# nabijecka1.net
KiCad netlist of a schematic drawn in EAGLE
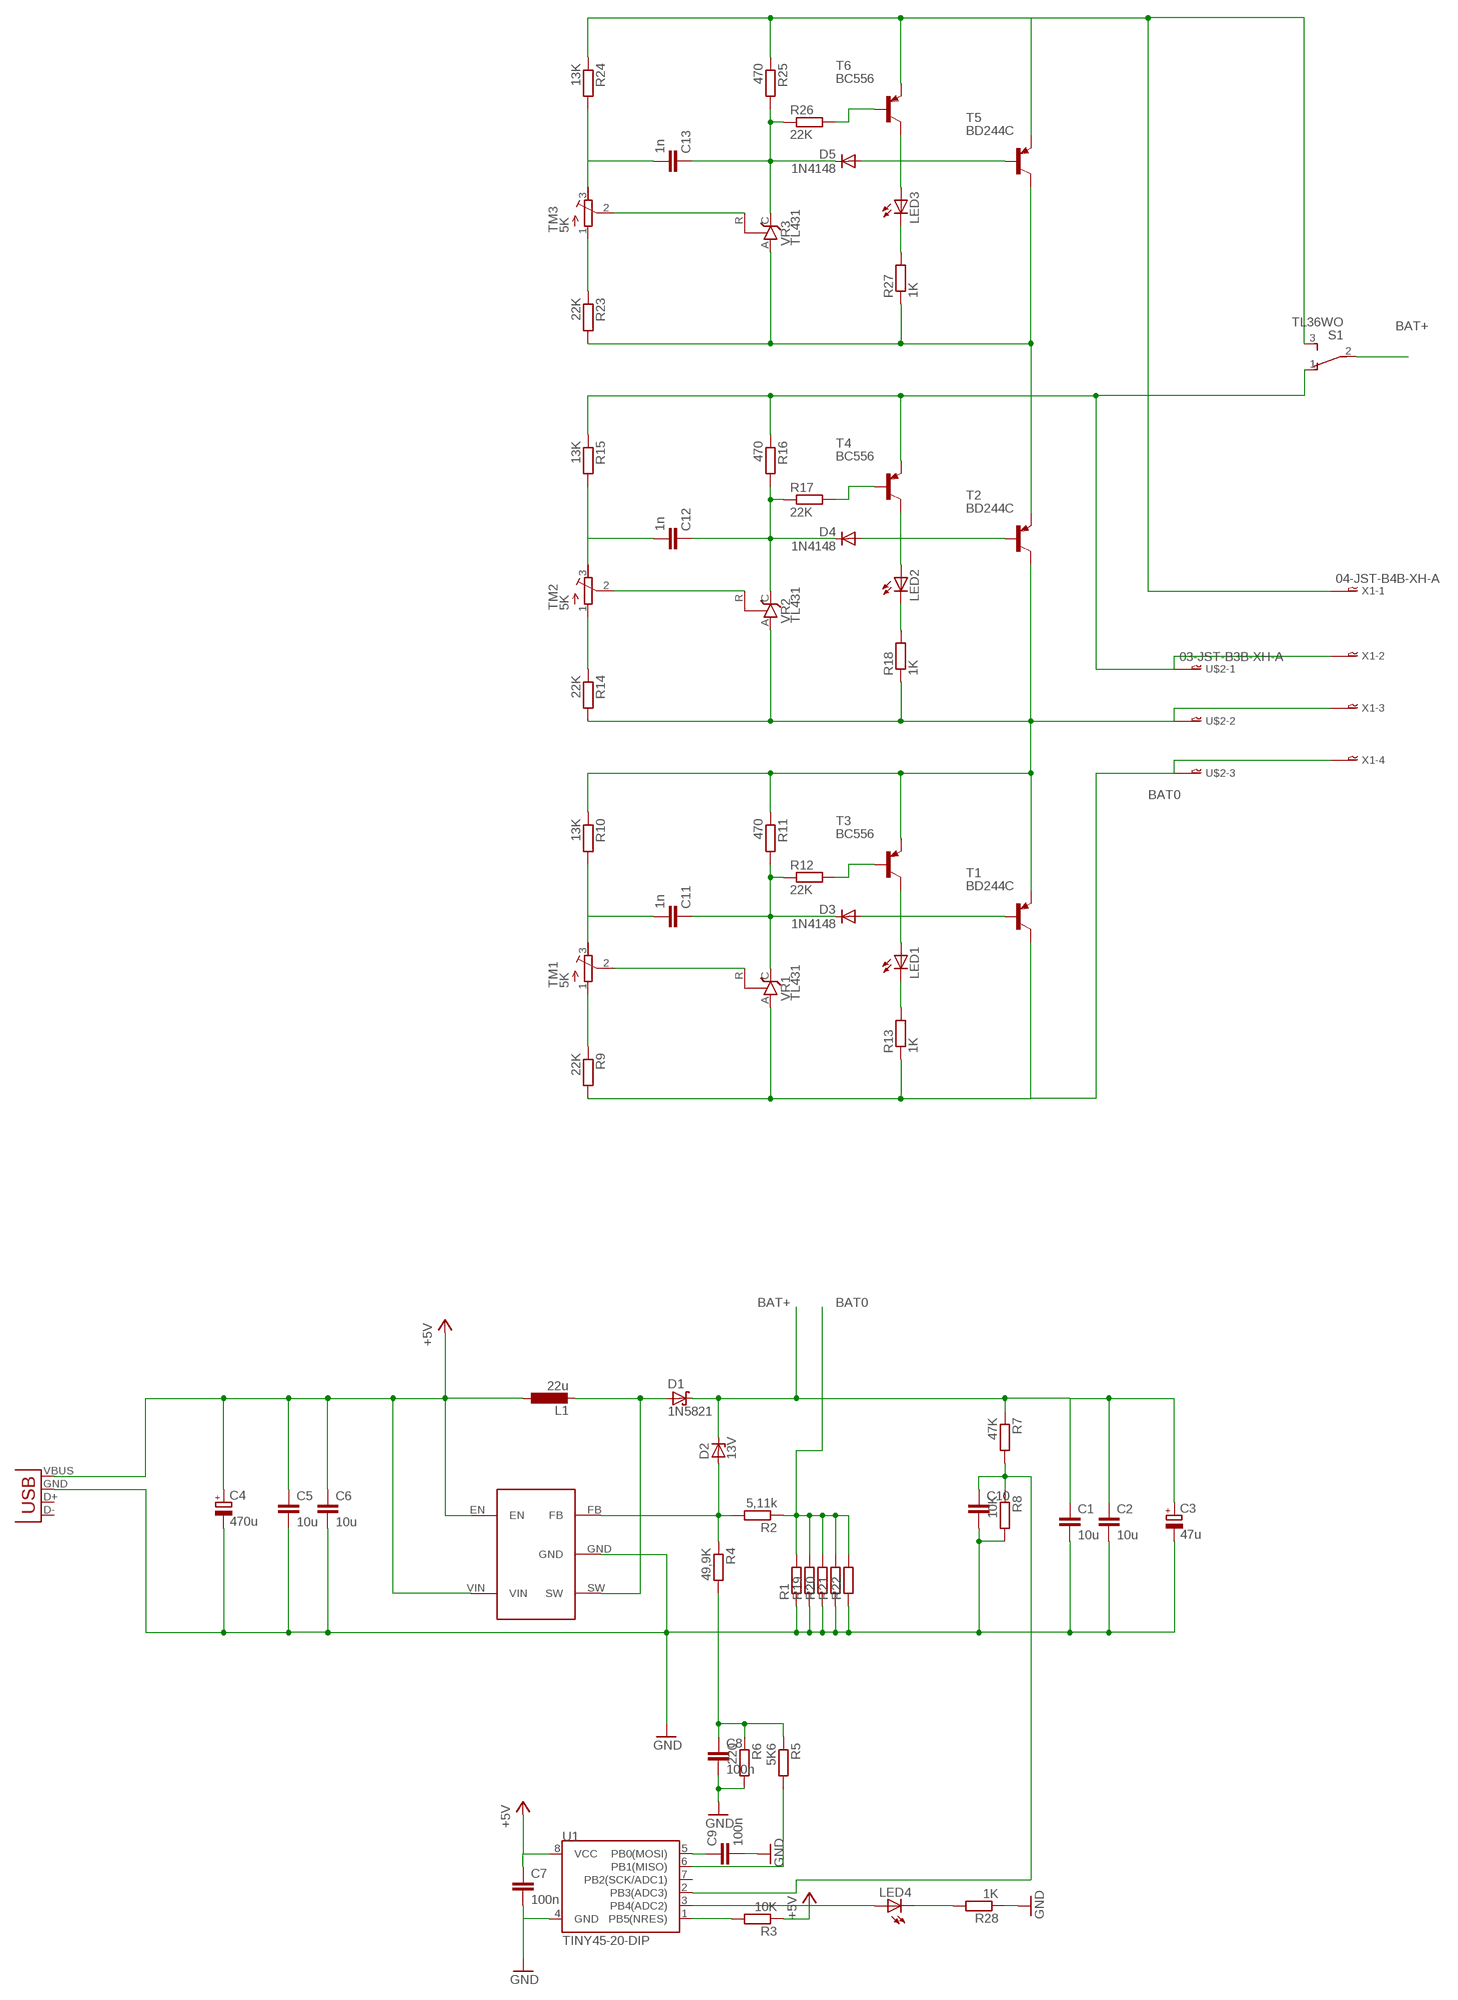
[diagram p0: schematic, sheet 1]

(export (version "E")
  (design (tool "Eeschema 10.0.6"))
  (components
    (comp (ref "C1")
      (value "10u")
      (footprint "eagle-import:C1206")
      (libsource (lib "eagle-import") (part "C-EUC1206"))
    )
    (comp (ref "C2")
      (value "10u")
      (footprint "eagle-import:C1206")
      (libsource (lib "eagle-import") (part "C-EUC1206"))
    )
    (comp (ref "C3")
      (value "47u")
      (footprint "eagle-import:E3,5-8")
      (libsource (lib "eagle-import") (part "CPOL-EUE3.5-8"))
    )
    (comp (ref "C4")
      (value "470u")
      (footprint "eagle-import:E3,5-8")
      (libsource (lib "eagle-import") (part "CPOL-EUE3.5-8"))
    )
    (comp (ref "C5")
      (value "10u")
      (footprint "eagle-import:C1206")
      (libsource (lib "eagle-import") (part "C-EUC1206"))
    )
    (comp (ref "C6")
      (value "10u")
      (footprint "eagle-import:C1206")
      (libsource (lib "eagle-import") (part "C-EUC1206"))
    )
    (comp (ref "C7")
      (value "100n")
      (footprint "eagle-import:C0805")
      (libsource (lib "eagle-import") (part "C-EUC0805"))
    )
    (comp (ref "C8")
      (value "100n")
      (footprint "eagle-import:C1206")
      (libsource (lib "eagle-import") (part "C-EUC1206"))
    )
    (comp (ref "C9")
      (value "100n")
      (footprint "eagle-import:C0805")
      (libsource (lib "eagle-import") (part "C-EUC0805"))
    )
    (comp (ref "C10")
      (value "C-EUC1206")
      (footprint "eagle-import:C1206")
      (libsource (lib "eagle-import") (part "C-EUC1206"))
    )
    (comp (ref "C11")
      (value "1n")
      (footprint "eagle-import:C1206")
      (libsource (lib "eagle-import") (part "C-EUC1206"))
    )
    (comp (ref "C12")
      (value "1n")
      (footprint "eagle-import:C1206")
      (libsource (lib "eagle-import") (part "C-EUC1206"))
    )
    (comp (ref "C13")
      (value "1n")
      (footprint "eagle-import:C1206")
      (libsource (lib "eagle-import") (part "C-EUC1206"))
    )
    (comp (ref "D1")
      (value "1N5821")
      (footprint "eagle-import:DO35-7")
      (libsource (lib "eagle-import") (part "SCHOTTKY-DIODEDO35-7"))
    )
    (comp (ref "D2")
      (value "13V")
      (footprint "eagle-import:SOD80C")
      (libsource (lib "eagle-import") (part "ZENER-DIODESOD80C"))
    )
    (comp (ref "D3")
      (value "1N4148")
      (footprint "eagle-import:SOD80C")
      (libsource (lib "eagle-import") (part "DIODE-SOD80C"))
    )
    (comp (ref "D4")
      (value "1N4148")
      (footprint "eagle-import:SOD80C")
      (libsource (lib "eagle-import") (part "DIODE-SOD80C"))
    )
    (comp (ref "D5")
      (value "1N4148")
      (footprint "eagle-import:SOD80C")
      (libsource (lib "eagle-import") (part "DIODE-SOD80C"))
    )
    (comp (ref "JP2")
      (value "USB-A-H")
      (footprint "eagle-import:USB-A-H")
      (libsource (lib "eagle-import") (part "USB-A-H"))
    )
    (comp (ref "L1")
      (value "22u")
      (footprint "eagle-import:POWER-CHOKE_WE-TPC")
      (libsource (lib "eagle-import") (part "L-EUWE-TPC"))
    )
    (comp (ref "LED1")
      (value "LED3MM")
      (footprint "eagle-import:LED3MM")
      (libsource (lib "eagle-import") (part "LED3MM"))
    )
    (comp (ref "LED2")
      (value "LED3MM")
      (footprint "eagle-import:LED3MM")
      (libsource (lib "eagle-import") (part "LED3MM"))
    )
    (comp (ref "LED3")
      (value "LED3MM")
      (footprint "eagle-import:LED3MM")
      (libsource (lib "eagle-import") (part "LED3MM"))
    )
    (comp (ref "LED4")
      (value "LED3MM")
      (footprint "eagle-import:LED3MM")
      (libsource (lib "eagle-import") (part "LED3MM"))
    )
    (comp (ref "R1")
      (value "R-EU_0204/7")
      (footprint "eagle-import:0204_7")
      (libsource (lib "eagle-import") (part "R-EU_0204/7"))
    )
    (comp (ref "R2")
      (value "5,11k")
      (footprint "eagle-import:0204_5")
      (libsource (lib "eagle-import") (part "R-EU_0204/5"))
    )
    (comp (ref "R3")
      (value "10K")
      (footprint "eagle-import:R0805")
      (libsource (lib "eagle-import") (part "R-EU_R0805"))
    )
    (comp (ref "R4")
      (value "49,9K")
      (footprint "eagle-import:0204_5")
      (libsource (lib "eagle-import") (part "R-EU_0204/5"))
    )
    (comp (ref "R5")
      (value "5K6")
      (footprint "eagle-import:R1206")
      (libsource (lib "eagle-import") (part "R-EU_R1206"))
    )
    (comp (ref "R6")
      (value "220")
      (footprint "eagle-import:R1206")
      (libsource (lib "eagle-import") (part "R-EU_R1206"))
    )
    (comp (ref "R7")
      (value "47K")
      (footprint "eagle-import:R1206")
      (libsource (lib "eagle-import") (part "R-EU_R1206"))
    )
    (comp (ref "R8")
      (value "10K")
      (footprint "eagle-import:R1206")
      (libsource (lib "eagle-import") (part "R-EU_R1206"))
    )
    (comp (ref "R9")
      (value "22K")
      (footprint "eagle-import:R1206")
      (libsource (lib "eagle-import") (part "R-EU_R1206"))
    )
    (comp (ref "R10")
      (value "13K")
      (footprint "eagle-import:R1206")
      (libsource (lib "eagle-import") (part "R-EU_R1206"))
    )
    (comp (ref "R11")
      (value "470")
      (footprint "eagle-import:R1206")
      (libsource (lib "eagle-import") (part "R-EU_R1206"))
    )
    (comp (ref "R12")
      (value "22K")
      (footprint "eagle-import:R0805")
      (libsource (lib "eagle-import") (part "R-EU_R0805"))
    )
    (comp (ref "R13")
      (value "1K")
      (footprint "eagle-import:R1206")
      (libsource (lib "eagle-import") (part "R-EU_R1206"))
    )
    (comp (ref "R14")
      (value "22K")
      (footprint "eagle-import:R1206")
      (libsource (lib "eagle-import") (part "R-EU_R1206"))
    )
    (comp (ref "R15")
      (value "13K")
      (footprint "eagle-import:R1206")
      (libsource (lib "eagle-import") (part "R-EU_R1206"))
    )
    (comp (ref "R16")
      (value "470")
      (footprint "eagle-import:R1206")
      (libsource (lib "eagle-import") (part "R-EU_R1206"))
    )
    (comp (ref "R17")
      (value "22K")
      (footprint "eagle-import:R0805")
      (libsource (lib "eagle-import") (part "R-EU_R0805"))
    )
    (comp (ref "R18")
      (value "1K")
      (footprint "eagle-import:R1206")
      (libsource (lib "eagle-import") (part "R-EU_R1206"))
    )
    (comp (ref "R19")
      (value "R-EU_0204/7")
      (footprint "eagle-import:0204_7")
      (libsource (lib "eagle-import") (part "R-EU_0204/7"))
    )
    (comp (ref "R20")
      (value "R-EU_0204/7")
      (footprint "eagle-import:0204_7")
      (libsource (lib "eagle-import") (part "R-EU_0204/7"))
    )
    (comp (ref "R21")
      (value "R-EU_0204/7")
      (footprint "eagle-import:0204_7")
      (libsource (lib "eagle-import") (part "R-EU_0204/7"))
    )
    (comp (ref "R22")
      (value "R-EU_0204/7")
      (footprint "eagle-import:0204_7")
      (libsource (lib "eagle-import") (part "R-EU_0204/7"))
    )
    (comp (ref "R23")
      (value "22K")
      (footprint "eagle-import:R1206")
      (libsource (lib "eagle-import") (part "R-EU_R1206"))
    )
    (comp (ref "R24")
      (value "13K")
      (footprint "eagle-import:R1206")
      (libsource (lib "eagle-import") (part "R-EU_R1206"))
    )
    (comp (ref "R25")
      (value "470")
      (footprint "eagle-import:R1206")
      (libsource (lib "eagle-import") (part "R-EU_R1206"))
    )
    (comp (ref "R26")
      (value "22K")
      (footprint "eagle-import:R0805")
      (libsource (lib "eagle-import") (part "R-EU_R0805"))
    )
    (comp (ref "R27")
      (value "1K")
      (footprint "eagle-import:R1206")
      (libsource (lib "eagle-import") (part "R-EU_R1206"))
    )
    (comp (ref "R28")
      (value "1K")
      (footprint "eagle-import:R1206")
      (libsource (lib "eagle-import") (part "R-EU_R1206"))
    )
    (comp (ref "S1")
      (value "TL36WO")
      (footprint "eagle-import:TL3XWO")
      (libsource (lib "eagle-import") (part "TL36WO"))
    )
    (comp (ref "T1")
      (value "BD244C")
      (footprint "eagle-import:TO220")
      (libsource (lib "eagle-import") (part "-PNP-TO220"))
    )
    (comp (ref "T2")
      (value "BD244C")
      (footprint "eagle-import:TO220")
      (libsource (lib "eagle-import") (part "-PNP-TO220"))
    )
    (comp (ref "T3")
      (value "BC556")
      (footprint "eagle-import:TO92-EBC")
      (libsource (lib "eagle-import") (part "-PNP-TO92-EBCBC556B"))
    )
    (comp (ref "T4")
      (value "BC556")
      (footprint "eagle-import:TO92-EBC")
      (libsource (lib "eagle-import") (part "-PNP-TO92-EBCBC556B"))
    )
    (comp (ref "T5")
      (value "BD244C")
      (footprint "eagle-import:TO220")
      (libsource (lib "eagle-import") (part "-PNP-TO220"))
    )
    (comp (ref "T6")
      (value "BC556")
      (footprint "eagle-import:TO92-EBC")
      (libsource (lib "eagle-import") (part "-PNP-TO92-EBCBC556B"))
    )
    (comp (ref "TM1")
      (value "5K")
      (footprint "eagle-import:RTRIM64P")
      (libsource (lib "eagle-import") (part "R-TRIMM64P"))
    )
    (comp (ref "TM2")
      (value "5K")
      (footprint "eagle-import:RTRIM64P")
      (libsource (lib "eagle-import") (part "R-TRIMM64P"))
    )
    (comp (ref "TM3")
      (value "5K")
      (footprint "eagle-import:RTRIM64P")
      (libsource (lib "eagle-import") (part "R-TRIMM64P"))
    )
    (comp (ref "U$1")
      (value "MIC2287")
      (footprint "eagle-import:MIC2287")
      (libsource (lib "eagle-import") (part "MIC2287"))
    )
    (comp (ref "U$2")
      (value "03-JST-B3B-XH-A")
      (footprint "eagle-import:B3B-XH")
      (libsource (lib "eagle-import") (part "03-JST-B3B-XH-A"))
    )
    (comp (ref "U1")
      (value "TINY45-20-DIP")
      (footprint "eagle-import:DIP08")
      (libsource (lib "eagle-import") (part "ATTINY45TINY45-20-DIP"))
    )
    (comp (ref "VR1")
      (value "TL431")
      (footprint "eagle-import:TO92-CLP")
      (libsource (lib "eagle-import") (part "TL431CLP"))
    )
    (comp (ref "VR2")
      (value "TL431")
      (footprint "eagle-import:TO92-CLP")
      (libsource (lib "eagle-import") (part "TL431CLP"))
    )
    (comp (ref "VR3")
      (value "TL431")
      (footprint "eagle-import:TO92-CLP")
      (libsource (lib "eagle-import") (part "TL431CLP"))
    )
    (comp (ref "X1")
      (value "04-JST-B4B-XH-A")
      (footprint "eagle-import:B4B-XH")
      (libsource (lib "eagle-import") (part "04-JST-B4B-XH-A"))
    )
  )
  (nets
    (net (code "1") (name "+5V") (class "Default")
      (node (ref "C4") (pin "+") (pinfunction "+_+") (pintype "passive"))
      (node (ref "C5") (pin "1") (pinfunction "1_1") (pintype "passive"))
      (node (ref "C6") (pin "1") (pinfunction "1_1") (pintype "passive"))
      (node (ref "C7") (pin "1") (pinfunction "1_1") (pintype "passive"))
      (node (ref "JP2") (pin "VBUS") (pinfunction "GND_VBUS") (pintype "bidirectional"))
      (node (ref "L1") (pin "1") (pinfunction "1_1") (pintype "passive"))
      (node (ref "R3") (pin "1") (pinfunction "1_1") (pintype "passive"))
      (node (ref "U$1") (pin "EN") (pinfunction "EN_EN") (pintype "bidirectional"))
      (node (ref "U$1") (pin "VIN") (pinfunction "VIN_VIN") (pintype "bidirectional"))
      (node (ref "U1") (pin "8") (pinfunction "VCC_8") (pintype "bidirectional"))
    )
    (net (code "2") (name "/BAT+") (class "Default")
      (node (ref "C1") (pin "1") (pinfunction "1_1") (pintype "passive"))
      (node (ref "C2") (pin "1") (pinfunction "1_1") (pintype "passive"))
      (node (ref "C3") (pin "+") (pinfunction "+_+") (pintype "passive"))
      (node (ref "D1") (pin "C") (pinfunction "C_C") (pintype "passive"))
      (node (ref "D2") (pin "C") (pinfunction "C_C") (pintype "passive"))
      (node (ref "R7") (pin "1") (pinfunction "1_1") (pintype "passive"))
      (node (ref "S1") (pin "2") (pinfunction "P_2") (pintype "passive"))
    )
    (net (code "3") (name "/BAT0") (class "Default")
      (node (ref "R1") (pin "2") (pinfunction "2_2") (pintype "passive"))
      (node (ref "R13") (pin "1") (pinfunction "1_1") (pintype "passive"))
      (node (ref "R19") (pin "2") (pinfunction "2_2") (pintype "passive"))
      (node (ref "R2") (pin "1") (pinfunction "1_1") (pintype "passive"))
      (node (ref "R20") (pin "2") (pinfunction "2_2") (pintype "passive"))
      (node (ref "R21") (pin "2") (pinfunction "2_2") (pintype "passive"))
      (node (ref "R22") (pin "2") (pinfunction "2_2") (pintype "passive"))
      (node (ref "R9") (pin "2") (pinfunction "2_2") (pintype "passive"))
      (node (ref "T1") (pin "2") (pinfunction "C_2") (pintype "passive"))
      (node (ref "U$2") (pin "P$3") (pinfunction "1_P$3") (pintype "passive"))
      (node (ref "VR1") (pin "A") (pinfunction "A_A") (pintype "passive"))
      (node (ref "X1") (pin "P$4") (pinfunction "1_P$4") (pintype "passive"))
    )
    (net (code "4") (name "GND") (class "Default")
      (node (ref "C1") (pin "2") (pinfunction "2_2") (pintype "passive"))
      (node (ref "C10") (pin "2") (pinfunction "2_2") (pintype "passive"))
      (node (ref "C2") (pin "2") (pinfunction "2_2") (pintype "passive"))
      (node (ref "C3") (pin "-") (pinfunction "-_-") (pintype "passive"))
      (node (ref "C4") (pin "-") (pinfunction "-_-") (pintype "passive"))
      (node (ref "C5") (pin "2") (pinfunction "2_2") (pintype "passive"))
      (node (ref "C6") (pin "2") (pinfunction "2_2") (pintype "passive"))
      (node (ref "C7") (pin "2") (pinfunction "2_2") (pintype "passive"))
      (node (ref "C8") (pin "2") (pinfunction "2_2") (pintype "passive"))
      (node (ref "C9") (pin "2") (pinfunction "2_2") (pintype "passive"))
      (node (ref "JP2") (pin "GND") (pinfunction "VBUS_GND") (pintype "bidirectional"))
      (node (ref "R1") (pin "1") (pinfunction "1_1") (pintype "passive"))
      (node (ref "R19") (pin "1") (pinfunction "1_1") (pintype "passive"))
      (node (ref "R20") (pin "1") (pinfunction "1_1") (pintype "passive"))
      (node (ref "R21") (pin "1") (pinfunction "1_1") (pintype "passive"))
      (node (ref "R22") (pin "1") (pinfunction "1_1") (pintype "passive"))
      (node (ref "R28") (pin "1") (pinfunction "1_1") (pintype "passive"))
      (node (ref "R6") (pin "2") (pinfunction "2_2") (pintype "passive"))
      (node (ref "R8") (pin "2") (pinfunction "2_2") (pintype "passive"))
      (node (ref "U$1") (pin "GND") (pinfunction "GND_GND") (pintype "bidirectional"))
      (node (ref "U1") (pin "4") (pinfunction "GND_4") (pintype "bidirectional"))
    )
    (net (code "5") (name "Net-(C8-Pad1)") (class "Default")
      (node (ref "C8") (pin "1") (pinfunction "1_1") (pintype "passive"))
      (node (ref "R4") (pin "2") (pinfunction "2_2") (pintype "passive"))
      (node (ref "R5") (pin "1") (pinfunction "1_1") (pintype "passive"))
      (node (ref "R6") (pin "1") (pinfunction "1_1") (pintype "passive"))
    )
    (net (code "6") (name "Net-(C11-Pad1)") (class "Default")
      (node (ref "C11") (pin "1") (pinfunction "1_1") (pintype "passive"))
      (node (ref "D3") (pin "C") (pinfunction "C_C") (pintype "passive"))
      (node (ref "R11") (pin "2") (pinfunction "2_2") (pintype "passive"))
      (node (ref "R12") (pin "1") (pinfunction "1_1") (pintype "passive"))
      (node (ref "VR1") (pin "C") (pinfunction "C_C") (pintype "passive"))
    )
    (net (code "7") (name "Net-(C12-Pad1)") (class "Default")
      (node (ref "C12") (pin "1") (pinfunction "1_1") (pintype "passive"))
      (node (ref "D4") (pin "C") (pinfunction "C_C") (pintype "passive"))
      (node (ref "R16") (pin "2") (pinfunction "2_2") (pintype "passive"))
      (node (ref "R17") (pin "1") (pinfunction "1_1") (pintype "passive"))
      (node (ref "VR2") (pin "C") (pinfunction "C_C") (pintype "passive"))
    )
    (net (code "8") (name "Net-(C13-Pad1)") (class "Default")
      (node (ref "C13") (pin "1") (pinfunction "1_1") (pintype "passive"))
      (node (ref "D5") (pin "C") (pinfunction "C_C") (pintype "passive"))
      (node (ref "R25") (pin "2") (pinfunction "2_2") (pintype "passive"))
      (node (ref "R26") (pin "1") (pinfunction "1_1") (pintype "passive"))
      (node (ref "VR3") (pin "C") (pinfunction "C_C") (pintype "passive"))
    )
    (net (code "9") (name "Net-(D1-PadA)") (class "Default")
      (node (ref "D1") (pin "A") (pinfunction "A_A") (pintype "passive"))
      (node (ref "L1") (pin "2") (pinfunction "2_2") (pintype "passive"))
      (node (ref "U$1") (pin "SW") (pinfunction "SW_SW") (pintype "bidirectional"))
    )
    (net (code "10") (name "Net-(D2-PadA)") (class "Default")
      (node (ref "D2") (pin "A") (pinfunction "A_A") (pintype "passive"))
      (node (ref "R2") (pin "2") (pinfunction "2_2") (pintype "passive"))
      (node (ref "R4") (pin "1") (pinfunction "1_1") (pintype "passive"))
      (node (ref "U$1") (pin "FB") (pinfunction "FB_FB") (pintype "bidirectional"))
    )
    (net (code "11") (name "Net-(LED1-C)") (class "Default")
      (node (ref "LED1") (pin "K") (pinfunction "C_K") (pintype "passive"))
      (node (ref "R13") (pin "2") (pinfunction "2_2") (pintype "passive"))
    )
    (net (code "12") (name "Net-(LED1-PadA)") (class "Default")
      (node (ref "LED1") (pin "A") (pinfunction "A_A") (pintype "passive"))
      (node (ref "T3") (pin "C") (pinfunction "C_C") (pintype "passive"))
    )
    (net (code "13") (name "Net-(LED2-C)") (class "Default")
      (node (ref "LED2") (pin "K") (pinfunction "C_K") (pintype "passive"))
      (node (ref "R18") (pin "2") (pinfunction "2_2") (pintype "passive"))
    )
    (net (code "14") (name "Net-(LED2-PadA)") (class "Default")
      (node (ref "LED2") (pin "A") (pinfunction "A_A") (pintype "passive"))
      (node (ref "T4") (pin "C") (pinfunction "C_C") (pintype "passive"))
    )
    (net (code "15") (name "Net-(LED3-C)") (class "Default")
      (node (ref "LED3") (pin "K") (pinfunction "C_K") (pintype "passive"))
      (node (ref "R27") (pin "2") (pinfunction "2_2") (pintype "passive"))
    )
    (net (code "16") (name "Net-(LED3-PadA)") (class "Default")
      (node (ref "LED3") (pin "A") (pinfunction "A_A") (pintype "passive"))
      (node (ref "T6") (pin "C") (pinfunction "C_C") (pintype "passive"))
    )
    (net (code "17") (name "Net-(LED4-C)") (class "Default")
      (node (ref "LED4") (pin "K") (pinfunction "C_K") (pintype "passive"))
      (node (ref "R28") (pin "2") (pinfunction "2_2") (pintype "passive"))
    )
    (net (code "18") (name "Net-(R12-Pad2)") (class "Default")
      (node (ref "R12") (pin "2") (pinfunction "2_2") (pintype "passive"))
      (node (ref "T3") (pin "B") (pinfunction "B_B") (pintype "passive"))
    )
    (net (code "19") (name "Net-(R17-Pad2)") (class "Default")
      (node (ref "R17") (pin "2") (pinfunction "2_2") (pintype "passive"))
      (node (ref "T4") (pin "B") (pinfunction "B_B") (pintype "passive"))
    )
    (net (code "20") (name "Net-(R26-Pad2)") (class "Default")
      (node (ref "R26") (pin "2") (pinfunction "2_2") (pintype "passive"))
      (node (ref "T6") (pin "B") (pinfunction "B_B") (pintype "passive"))
    )
    (net (code "21") (name "Net-(S1-O)") (class "Default")
      (node (ref "R15") (pin "1") (pinfunction "1_1") (pintype "passive"))
      (node (ref "R16") (pin "1") (pinfunction "1_1") (pintype "passive"))
      (node (ref "R23") (pin "2") (pinfunction "2_2") (pintype "passive"))
      (node (ref "R27") (pin "1") (pinfunction "1_1") (pintype "passive"))
      (node (ref "S1") (pin "1") (pinfunction "O_1") (pintype "passive"))
      (node (ref "T2") (pin "3") (pinfunction "E_3") (pintype "passive"))
      (node (ref "T4") (pin "E") (pinfunction "E_E") (pintype "passive"))
      (node (ref "T5") (pin "2") (pinfunction "C_2") (pintype "passive"))
      (node (ref "U$2") (pin "P$1") (pinfunction "1_P$1") (pintype "passive"))
      (node (ref "VR3") (pin "A") (pinfunction "A_A") (pintype "passive"))
      (node (ref "X1") (pin "P$2") (pinfunction "1_P$2") (pintype "passive"))
    )
    (net (code "22") (name "Net-(S1-S)") (class "Default")
      (node (ref "R24") (pin "1") (pinfunction "1_1") (pintype "passive"))
      (node (ref "R25") (pin "1") (pinfunction "1_1") (pintype "passive"))
      (node (ref "S1") (pin "3") (pinfunction "S_3") (pintype "passive"))
      (node (ref "T5") (pin "3") (pinfunction "E_3") (pintype "passive"))
      (node (ref "T6") (pin "E") (pinfunction "E_E") (pintype "passive"))
      (node (ref "X1") (pin "P$1") (pinfunction "1_P$1") (pintype "passive"))
    )
    (net (code "23") (name "Net-(T1-B)") (class "Default")
      (node (ref "D3") (pin "A") (pinfunction "A_A") (pintype "passive"))
      (node (ref "T1") (pin "1") (pinfunction "B_1") (pintype "passive"))
    )
    (net (code "24") (name "Net-(T1-E)") (class "Default")
      (node (ref "R10") (pin "1") (pinfunction "1_1") (pintype "passive"))
      (node (ref "R11") (pin "1") (pinfunction "1_1") (pintype "passive"))
      (node (ref "R14") (pin "2") (pinfunction "2_2") (pintype "passive"))
      (node (ref "R18") (pin "1") (pinfunction "1_1") (pintype "passive"))
      (node (ref "T1") (pin "3") (pinfunction "E_3") (pintype "passive"))
      (node (ref "T2") (pin "2") (pinfunction "C_2") (pintype "passive"))
      (node (ref "T3") (pin "E") (pinfunction "E_E") (pintype "passive"))
      (node (ref "U$2") (pin "P$2") (pinfunction "1_P$2") (pintype "passive"))
      (node (ref "VR2") (pin "A") (pinfunction "A_A") (pintype "passive"))
      (node (ref "X1") (pin "P$3") (pinfunction "1_P$3") (pintype "passive"))
    )
    (net (code "25") (name "Net-(T2-B)") (class "Default")
      (node (ref "D4") (pin "A") (pinfunction "A_A") (pintype "passive"))
      (node (ref "T2") (pin "1") (pinfunction "B_1") (pintype "passive"))
    )
    (net (code "26") (name "Net-(T5-B)") (class "Default")
      (node (ref "D5") (pin "A") (pinfunction "A_A") (pintype "passive"))
      (node (ref "T5") (pin "1") (pinfunction "B_1") (pintype "passive"))
    )
    (net (code "27") (name "Net-(TM1-A)") (class "Default")
      (node (ref "C11") (pin "2") (pinfunction "2_2") (pintype "passive"))
      (node (ref "R10") (pin "2") (pinfunction "2_2") (pintype "passive"))
      (node (ref "TM1") (pin "3") (pinfunction "A_3") (pintype "passive"))
    )
    (net (code "28") (name "Net-(TM1-E)") (class "Default")
      (node (ref "R9") (pin "1") (pinfunction "1_1") (pintype "passive"))
      (node (ref "TM1") (pin "1") (pinfunction "E_1") (pintype "passive"))
    )
    (net (code "29") (name "Net-(TM1-S)") (class "Default")
      (node (ref "TM1") (pin "2") (pinfunction "S_2") (pintype "passive"))
      (node (ref "VR1") (pin "R") (pinfunction "R_R") (pintype "passive"))
    )
    (net (code "30") (name "Net-(TM2-A)") (class "Default")
      (node (ref "C12") (pin "2") (pinfunction "2_2") (pintype "passive"))
      (node (ref "R15") (pin "2") (pinfunction "2_2") (pintype "passive"))
      (node (ref "TM2") (pin "3") (pinfunction "A_3") (pintype "passive"))
    )
    (net (code "31") (name "Net-(TM2-E)") (class "Default")
      (node (ref "R14") (pin "1") (pinfunction "1_1") (pintype "passive"))
      (node (ref "TM2") (pin "1") (pinfunction "E_1") (pintype "passive"))
    )
    (net (code "32") (name "Net-(TM2-S)") (class "Default")
      (node (ref "TM2") (pin "2") (pinfunction "S_2") (pintype "passive"))
      (node (ref "VR2") (pin "R") (pinfunction "R_R") (pintype "passive"))
    )
    (net (code "33") (name "Net-(TM3-A)") (class "Default")
      (node (ref "C13") (pin "2") (pinfunction "2_2") (pintype "passive"))
      (node (ref "R24") (pin "2") (pinfunction "2_2") (pintype "passive"))
      (node (ref "TM3") (pin "3") (pinfunction "A_3") (pintype "passive"))
    )
    (net (code "34") (name "Net-(TM3-E)") (class "Default")
      (node (ref "R23") (pin "1") (pinfunction "1_1") (pintype "passive"))
      (node (ref "TM3") (pin "1") (pinfunction "E_1") (pintype "passive"))
    )
    (net (code "35") (name "Net-(TM3-S)") (class "Default")
      (node (ref "TM3") (pin "2") (pinfunction "S_2") (pintype "passive"))
      (node (ref "VR3") (pin "R") (pinfunction "R_R") (pintype "passive"))
    )
    (net (code "36") (name "Net-(U1-PB0(MOSI))") (class "Default")
      (node (ref "C9") (pin "1") (pinfunction "1_1") (pintype "passive"))
      (node (ref "U1") (pin "5") (pinfunction "PB0(MOSI)_5") (pintype "bidirectional"))
    )
    (net (code "37") (name "Net-(U1-PB1(MISO))") (class "Default")
      (node (ref "R5") (pin "2") (pinfunction "2_2") (pintype "passive"))
      (node (ref "U1") (pin "6") (pinfunction "PB1(MISO)_6") (pintype "bidirectional"))
    )
    (net (code "38") (name "Net-(U1-PB3(ADC3))") (class "Default")
      (node (ref "C10") (pin "1") (pinfunction "1_1") (pintype "passive"))
      (node (ref "R7") (pin "2") (pinfunction "2_2") (pintype "passive"))
      (node (ref "R8") (pin "1") (pinfunction "1_1") (pintype "passive"))
      (node (ref "U1") (pin "2") (pinfunction "PB3(ADC3)_2") (pintype "bidirectional"))
    )
    (net (code "39") (name "Net-(U1-PB4(ADC2))") (class "Default")
      (node (ref "LED4") (pin "A") (pinfunction "A_A") (pintype "passive"))
      (node (ref "U1") (pin "3") (pinfunction "PB4(ADC2)_3") (pintype "bidirectional"))
    )
    (net (code "40") (name "Net-(U1-PB5(NRES))") (class "Default")
      (node (ref "R3") (pin "2") (pinfunction "2_2") (pintype "passive"))
      (node (ref "U1") (pin "1") (pinfunction "PB5(NRES)_1") (pintype "bidirectional"))
    )
    (net (code "41") (name "unconnected-(JP2-D+-PadD-)") (class "Default")
      (node (ref "JP2") (pin "D-") (pinfunction "D+_D-") (pintype "bidirectional"))
    )
    (net (code "42") (name "unconnected-(JP2-D--PadD+)") (class "Default")
      (node (ref "JP2") (pin "D+") (pinfunction "D-_D+") (pintype "bidirectional"))
    )
    (net (code "43") (name "unconnected-(U1-PB2(SCK{slash}ADC1)-Pad7)") (class "Default")
      (node (ref "U1") (pin "7") (pinfunction "PB2(SCK/ADC1)_7") (pintype "bidirectional"))
    )
  )
)
